# vacuum-cleaner.net
KiCad netlist of a schematic drawn in EAGLE
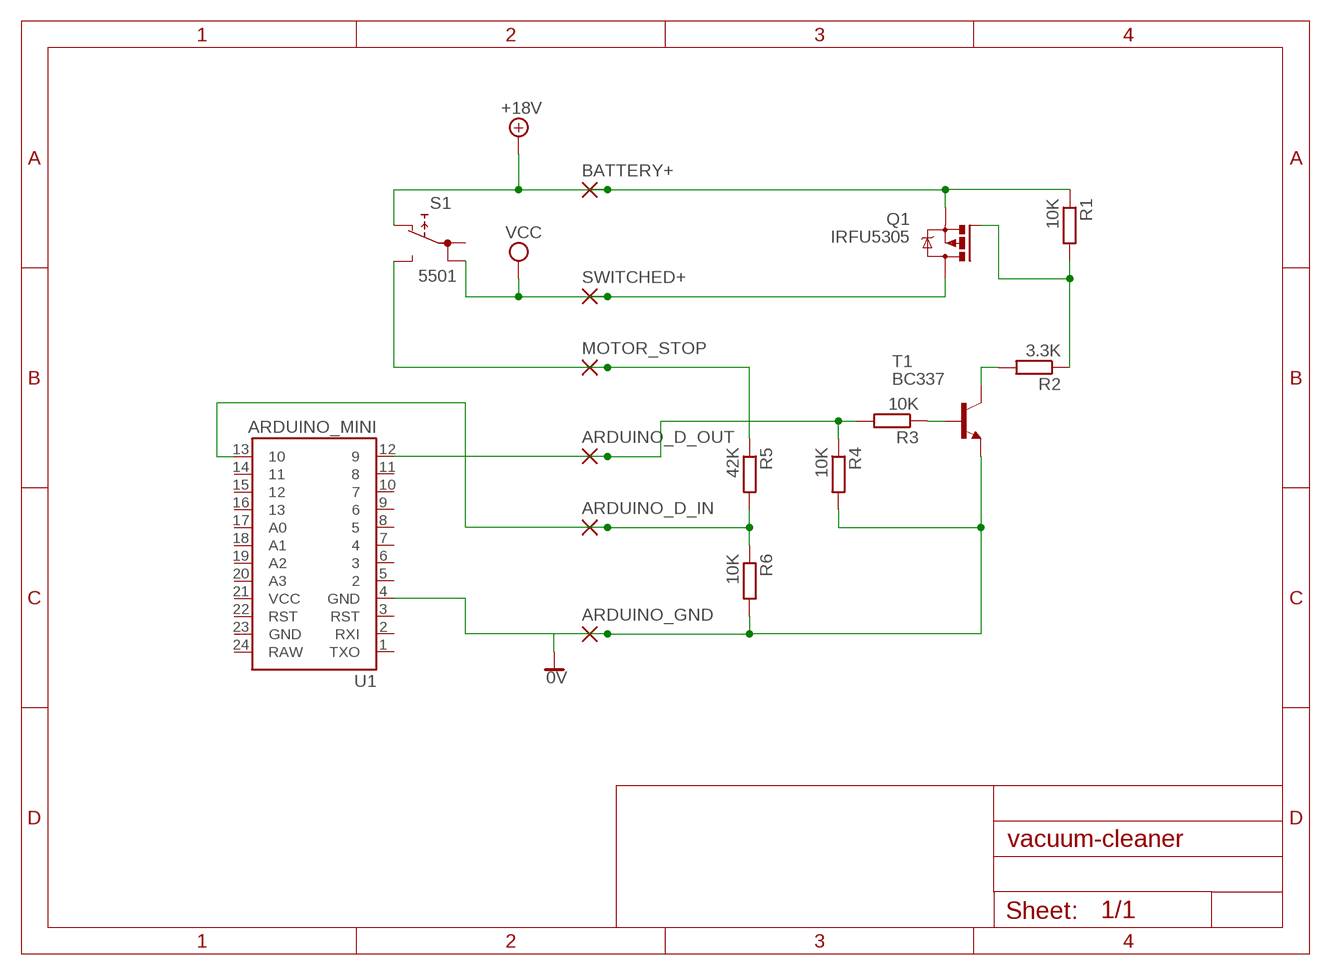
[diagram p0: schematic, sheet 1]

(export (version "E")
  (design (tool "Eeschema 10.0.6"))
  (components
    (comp (ref "ARDUINO_D_IN")
      (value "2,54/0,8")
      (footprint "eagle-import:2,54_0,8")
      (libsource (lib "eagle-import") (part "2,54/0,8"))
    )
    (comp (ref "ARDUINO_D_OUT")
      (value "2,54/0,8")
      (footprint "eagle-import:2,54_0,8")
      (libsource (lib "eagle-import") (part "2,54/0,8"))
    )
    (comp (ref "ARDUINO_GND")
      (value "2,54/0,8")
      (footprint "eagle-import:2,54_0,8")
      (libsource (lib "eagle-import") (part "2,54/0,8"))
    )
    (comp (ref "BATTERY+")
      (value "2,54/0,8")
      (footprint "eagle-import:2,54_0,8")
      (libsource (lib "eagle-import") (part "2,54/0,8"))
    )
    (comp (ref "MOTOR_STOP")
      (value "2,54/0,8")
      (footprint "eagle-import:2,54_0,8")
      (libsource (lib "eagle-import") (part "2,54/0,8"))
    )
    (comp (ref "Q1")
      (value "IRFU5305")
      (footprint "eagle-import:I-PAK_TO251AA")
      (libsource (lib "eagle-import") (part "IRF?5305U"))
    )
    (comp (ref "R1")
      (value "10K")
      (footprint "eagle-import:0207_10")
      (libsource (lib "eagle-import") (part "R-EU_0207/10"))
    )
    (comp (ref "R2")
      (value "3.3K")
      (footprint "eagle-import:0207_10")
      (libsource (lib "eagle-import") (part "R-EU_0207/10"))
    )
    (comp (ref "R3")
      (value "10K")
      (footprint "eagle-import:0207_10")
      (libsource (lib "eagle-import") (part "R-EU_0207/10"))
    )
    (comp (ref "R4")
      (value "10K")
      (footprint "eagle-import:0207_10")
      (libsource (lib "eagle-import") (part "R-EU_0207/10"))
    )
    (comp (ref "R5")
      (value "42K")
      (footprint "eagle-import:0207_10")
      (libsource (lib "eagle-import") (part "R-EU_0207/10"))
    )
    (comp (ref "R6")
      (value "10K")
      (footprint "eagle-import:0207_10")
      (libsource (lib "eagle-import") (part "R-EU_0207/10"))
    )
    (comp (ref "S1")
      (value "5501")
      (footprint "eagle-import:5501")
      (libsource (lib "eagle-import") (part "55?01"))
    )
    (comp (ref "SWITCHED+")
      (value "2,54/0,8")
      (footprint "eagle-import:2,54_0,8")
      (libsource (lib "eagle-import") (part "2,54/0,8"))
    )
    (comp (ref "T1")
      (value "BC337")
      (footprint "eagle-import:TO92")
      (libsource (lib "eagle-import") (part "BC337"))
    )
    (comp (ref "U1")
      (value "ARDUINO_MINI")
      (footprint "eagle-import:ARDUINO_MINI")
      (libsource (lib "eagle-import") (part "ARDUINO_MINI"))
    )
  )
  (nets
    (net (code "1") (name "+18V") (class "Default")
      (node (ref "BATTERY+") (pin "1") (pinfunction "P_1") (pintype "passive"))
      (node (ref "Q1") (pin "3") (pinfunction "S_3") (pintype "passive"))
      (node (ref "R1") (pin "1") (pinfunction "1_1") (pintype "passive"))
      (node (ref "S1") (pin "NC") (pinfunction "NC_NC") (pintype "passive"))
    )
    (net (code "2") (name "0V") (class "Default")
      (node (ref "ARDUINO_GND") (pin "1") (pinfunction "P_1") (pintype "passive"))
      (node (ref "R4") (pin "2") (pinfunction "2_2") (pintype "passive"))
      (node (ref "R6") (pin "2") (pinfunction "2_2") (pintype "passive"))
      (node (ref "T1") (pin "1") (pinfunction "E_1") (pintype "passive"))
      (node (ref "U1") (pin "4") (pinfunction "GND_4") (pintype "bidirectional"))
    )
    (net (code "3") (name "Net-(ARDUINO_D_IN-P)") (class "Default")
      (node (ref "ARDUINO_D_IN") (pin "1") (pinfunction "P_1") (pintype "passive"))
      (node (ref "R5") (pin "2") (pinfunction "2_2") (pintype "passive"))
      (node (ref "R6") (pin "1") (pinfunction "1_1") (pintype "passive"))
      (node (ref "U1") (pin "13") (pinfunction "10_13") (pintype "bidirectional"))
    )
    (net (code "4") (name "Net-(ARDUINO_D_OUT-P)") (class "Default")
      (node (ref "ARDUINO_D_OUT") (pin "1") (pinfunction "P_1") (pintype "passive"))
      (node (ref "R3") (pin "2") (pinfunction "2_2") (pintype "passive"))
      (node (ref "R4") (pin "1") (pinfunction "1_1") (pintype "passive"))
      (node (ref "U1") (pin "12") (pinfunction "9_12") (pintype "bidirectional"))
    )
    (net (code "5") (name "Net-(MOTOR_STOP-P)") (class "Default")
      (node (ref "MOTOR_STOP") (pin "1") (pinfunction "P_1") (pintype "passive"))
      (node (ref "R5") (pin "1") (pinfunction "1_1") (pintype "passive"))
      (node (ref "S1") (pin "NO") (pinfunction "NO_NO") (pintype "passive"))
    )
    (net (code "6") (name "Net-(Q1-G)") (class "Default")
      (node (ref "Q1") (pin "1") (pinfunction "G_1") (pintype "passive"))
      (node (ref "R1") (pin "2") (pinfunction "2_2") (pintype "passive"))
      (node (ref "R2") (pin "1") (pinfunction "1_1") (pintype "passive"))
    )
    (net (code "7") (name "Net-(T1-B)") (class "Default")
      (node (ref "R3") (pin "1") (pinfunction "1_1") (pintype "passive"))
      (node (ref "T1") (pin "2") (pinfunction "B_2") (pintype "passive"))
    )
    (net (code "8") (name "Net-(T1-C)") (class "Default")
      (node (ref "R2") (pin "2") (pinfunction "2_2") (pintype "passive"))
      (node (ref "T1") (pin "3") (pinfunction "C_3") (pintype "passive"))
    )
    (net (code "9") (name "VCC") (class "Default")
      (node (ref "Q1") (pin "2") (pinfunction "D_2") (pintype "passive"))
      (node (ref "S1") (pin "1B") (pinfunction "1B_1B") (pintype "passive"))
      (node (ref "SWITCHED+") (pin "1") (pinfunction "P_1") (pintype "passive"))
    )
    (net (code "10") (name "unconnected-(S1-Pad1A)") (class "Default")
      (node (ref "S1") (pin "1A") (pinfunction "1A_1A") (pintype "passive"))
    )
    (net (code "11") (name "unconnected-(U1-2-Pad5)") (class "Default")
      (node (ref "U1") (pin "5") (pinfunction "2_5") (pintype "bidirectional"))
    )
    (net (code "12") (name "unconnected-(U1-3-Pad6)") (class "Default")
      (node (ref "U1") (pin "6") (pinfunction "3_6") (pintype "bidirectional"))
    )
    (net (code "13") (name "unconnected-(U1-4-Pad7)") (class "Default")
      (node (ref "U1") (pin "7") (pinfunction "4_7") (pintype "bidirectional"))
    )
    (net (code "14") (name "unconnected-(U1-5-Pad8)") (class "Default")
      (node (ref "U1") (pin "8") (pinfunction "5_8") (pintype "bidirectional"))
    )
    (net (code "15") (name "unconnected-(U1-6-Pad9)") (class "Default")
      (node (ref "U1") (pin "9") (pinfunction "6_9") (pintype "bidirectional"))
    )
    (net (code "16") (name "unconnected-(U1-7-Pad10)") (class "Default")
      (node (ref "U1") (pin "10") (pinfunction "7_10") (pintype "bidirectional"))
    )
    (net (code "17") (name "unconnected-(U1-8-Pad11)") (class "Default")
      (node (ref "U1") (pin "11") (pinfunction "8_11") (pintype "bidirectional"))
    )
    (net (code "18") (name "unconnected-(U1-11-Pad14)") (class "Default")
      (node (ref "U1") (pin "14") (pinfunction "11_14") (pintype "bidirectional"))
    )
    (net (code "19") (name "unconnected-(U1-12-Pad15)") (class "Default")
      (node (ref "U1") (pin "15") (pinfunction "12_15") (pintype "bidirectional"))
    )
    (net (code "20") (name "unconnected-(U1-13-Pad16)") (class "Default")
      (node (ref "U1") (pin "16") (pinfunction "13_16") (pintype "bidirectional"))
    )
    (net (code "21") (name "unconnected-(U1-A0-Pad17)") (class "Default")
      (node (ref "U1") (pin "17") (pinfunction "A0_17") (pintype "bidirectional"))
    )
    (net (code "22") (name "unconnected-(U1-A1-Pad18)") (class "Default")
      (node (ref "U1") (pin "18") (pinfunction "A1_18") (pintype "bidirectional"))
    )
    (net (code "23") (name "unconnected-(U1-A2-Pad19)") (class "Default")
      (node (ref "U1") (pin "19") (pinfunction "A2_19") (pintype "bidirectional"))
    )
    (net (code "24") (name "unconnected-(U1-A3-Pad20)") (class "Default")
      (node (ref "U1") (pin "20") (pinfunction "A3_20") (pintype "bidirectional"))
    )
    (net (code "25") (name "unconnected-(U1-GND-Pad23)") (class "Default")
      (node (ref "U1") (pin "23") (pinfunction "GND_23") (pintype "bidirectional"))
    )
    (net (code "26") (name "unconnected-(U1-RAW-Pad24)") (class "Default")
      (node (ref "U1") (pin "24") (pinfunction "RAW_24") (pintype "bidirectional"))
    )
    (net (code "27") (name "unconnected-(U1-RST-Pad3)") (class "Default")
      (node (ref "U1") (pin "3") (pinfunction "RST_3") (pintype "bidirectional"))
    )
    (net (code "28") (name "unconnected-(U1-RST-Pad22)") (class "Default")
      (node (ref "U1") (pin "22") (pinfunction "RST_22") (pintype "bidirectional"))
    )
    (net (code "29") (name "unconnected-(U1-RXI-Pad2)") (class "Default")
      (node (ref "U1") (pin "2") (pinfunction "RXI_2") (pintype "bidirectional"))
    )
    (net (code "30") (name "unconnected-(U1-TXO-Pad1)") (class "Default")
      (node (ref "U1") (pin "1") (pinfunction "TXO_1") (pintype "bidirectional"))
    )
    (net (code "31") (name "unconnected-(U1-VCC-Pad21)") (class "Default")
      (node (ref "U1") (pin "21") (pinfunction "VCC_21") (pintype "bidirectional"))
    )
  )
)
